# raspdoor.net
KiCad netlist of a schematic drawn in EAGLE
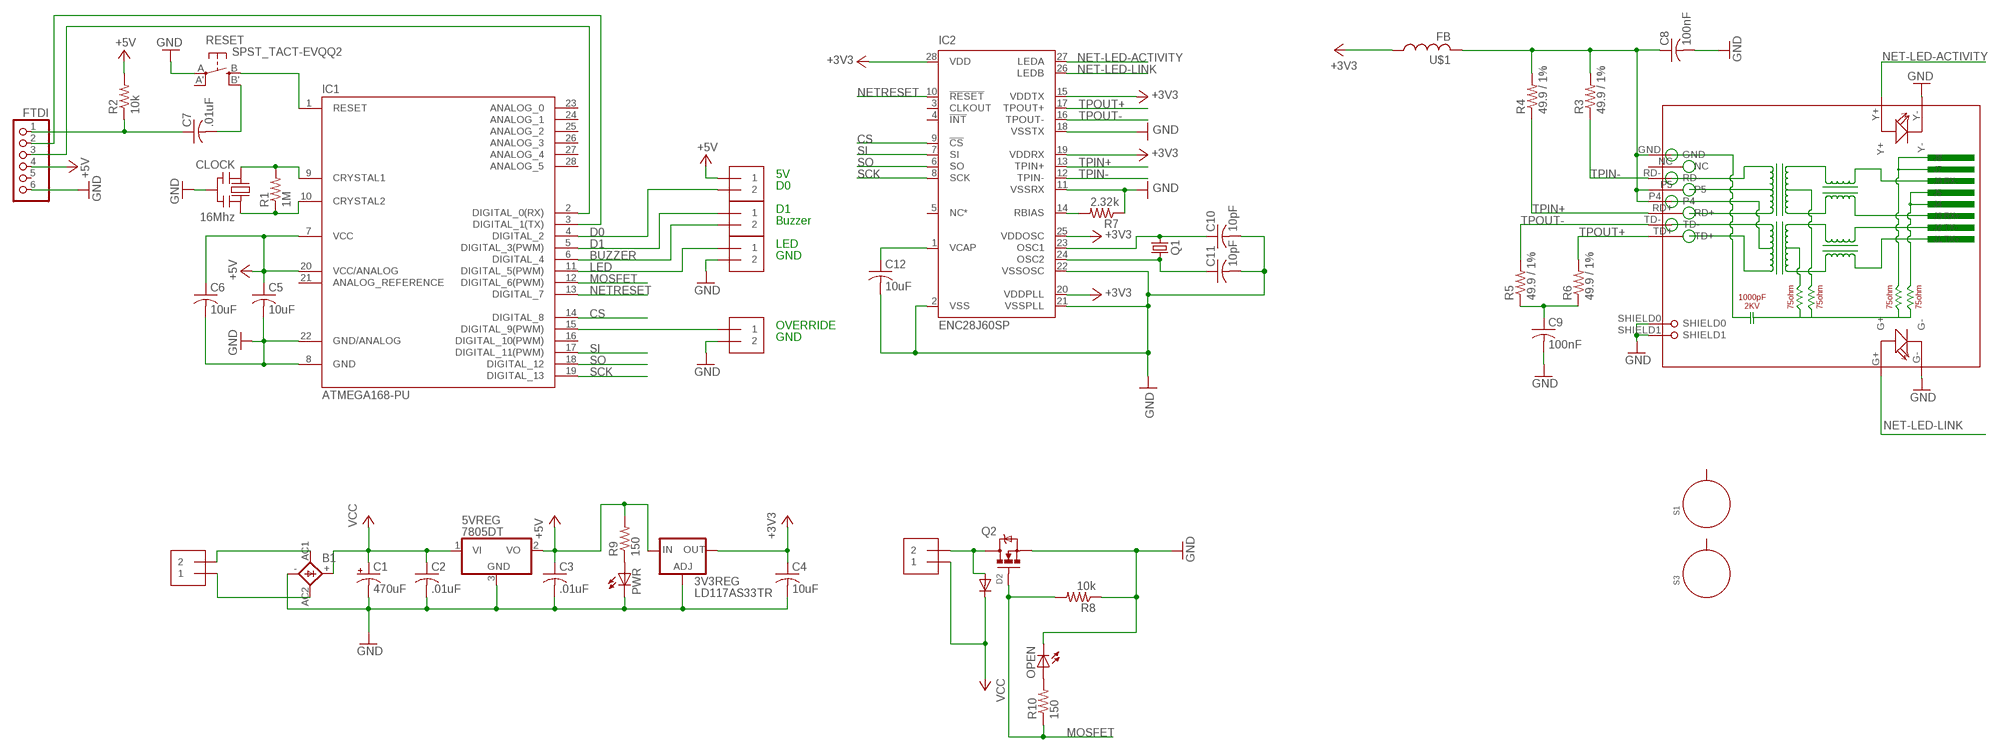
[diagram p0: schematic, sheet 1]

(export (version "E")
  (design (tool "Eeschema 10.0.6"))
  (components
    (comp (ref "3V3REG")
      (value "LD117AS33TR")
      (footprint "eagle-import:SOT223")
      (libsource (lib "eagle-import") (part "LD117A?S33TR"))
    )
    (comp (ref "5VREG")
      (value "7805DT")
      (footprint "eagle-import:TO252")
      (libsource (lib "eagle-import") (part "78DT05"))
    )
    (comp (ref "B1")
      (value "2KBB")
      (footprint "eagle-import:2KBB")
      (libsource (lib "eagle-import") (part "2KBB"))
    )
    (comp (ref "C1")
      (value "470uF")
      (footprint "eagle-import:153CLV-0810")
      (libsource (lib "eagle-import") (part "CPOL-US153CLV-0810"))
    )
    (comp (ref "C2")
      (value ".01uF")
      (footprint "eagle-import:C0805")
      (libsource (lib "eagle-import") (part "C-USC0805"))
    )
    (comp (ref "C3")
      (value ".01uF")
      (footprint "eagle-import:C0805")
      (libsource (lib "eagle-import") (part "C-USC0805"))
    )
    (comp (ref "C4")
      (value "10uF")
      (footprint "eagle-import:C0805")
      (libsource (lib "eagle-import") (part "C-USC0805"))
    )
    (comp (ref "C5")
      (value "10uF")
      (footprint "eagle-import:C0805")
      (libsource (lib "eagle-import") (part "C-USC0805"))
    )
    (comp (ref "C6")
      (value "10uF")
      (footprint "eagle-import:C0805")
      (libsource (lib "eagle-import") (part "C-USC0805"))
    )
    (comp (ref "C7")
      (value ".01uF")
      (footprint "eagle-import:C0805")
      (libsource (lib "eagle-import") (part "C-USC0805"))
    )
    (comp (ref "C8")
      (value "100nF")
      (footprint "eagle-import:C0805")
      (libsource (lib "eagle-import") (part "C-USC0805"))
    )
    (comp (ref "C9")
      (value "100nF")
      (footprint "eagle-import:C0805")
      (libsource (lib "eagle-import") (part "C-USC0805"))
    )
    (comp (ref "C10")
      (value "10pF")
      (footprint "eagle-import:C0805")
      (libsource (lib "eagle-import") (part "C-USC0805"))
    )
    (comp (ref "C11")
      (value "10pF")
      (footprint "eagle-import:C0805")
      (libsource (lib "eagle-import") (part "C-USC0805"))
    )
    (comp (ref "C12")
      (value "10uF")
      (footprint "eagle-import:C0805")
      (libsource (lib "eagle-import") (part "C-USC0805"))
    )
    (comp (ref "CLOCK")
      (value "16Mhz")
      (footprint "eagle-import:CERM_OSC")
      (libsource (lib "eagle-import") (part "CERMOSCILL-THM"))
    )
    (comp (ref "D2")
      (value "DIODESMA")
      (footprint "eagle-import:SMADIODE")
      (libsource (lib "eagle-import") (part "DIODESMA"))
    )
    (comp (ref "FTDI")
      (value "PINHD-1X6")
      (footprint "eagle-import:1X06")
      (libsource (lib "eagle-import") (part "PINHD-1X6"))
    )
    (comp (ref "IC1")
      (value "ATMEGA168-PU")
      (footprint "eagle-import:DIL28-3")
      (libsource (lib "eagle-import") (part "ATMEGA168-PU"))
    )
    (comp (ref "IC2")
      (value "ENC28J60SP")
      (footprint "eagle-import:DIL28-3")
      (fields (field (name "MF") "MICROCHIP") (field (name "MPN") "ENC28J60/SP"))
      (libsource (lib "eagle-import") (part "ENC28J60SP"))
    )
    (comp (ref "J1")
      (value "1X2-3.5MM")
      (footprint "eagle-import:1X2-3.5MM")
      (libsource (lib "eagle-import") (part "1X2-3.5MM"))
    )
    (comp (ref "J2")
      (value "1X2-3.5MM")
      (footprint "eagle-import:1X2-3.5MM")
      (libsource (lib "eagle-import") (part "1X2-3.5MM"))
    )
    (comp (ref "J3")
      (value "1X2-3.5MM")
      (footprint "eagle-import:1X2-3.5MM")
      (libsource (lib "eagle-import") (part "1X2-3.5MM"))
    )
    (comp (ref "J4")
      (value "1X2-3.5MM")
      (footprint "eagle-import:1X2-3.5MM")
      (libsource (lib "eagle-import") (part "1X2-3.5MM"))
    )
    (comp (ref "J5")
      (value "1X2-3.5MM")
      (footprint "eagle-import:1X2-3.5MM")
      (libsource (lib "eagle-import") (part "1X2-3.5MM"))
    )
    (comp (ref "J6")
      (value "1X2-3.5MM")
      (footprint "eagle-import:1X2-3.5MM")
      (libsource (lib "eagle-import") (part "1X2-3.5MM"))
    )
    (comp (ref "OPEN")
      (value "LEDCHIPLED_0805")
      (footprint "eagle-import:CHIPLED_0805")
      (libsource (lib "eagle-import") (part "LEDCHIPLED_0805"))
    )
    (comp (ref "PWR")
      (value "LEDCHIPLED_0805")
      (footprint "eagle-import:CHIPLED_0805")
      (libsource (lib "eagle-import") (part "LEDCHIPLED_0805"))
    )
    (comp (ref "Q1")
      (value "CRYSTALHC49S")
      (footprint "eagle-import:HC49_S")
      (libsource (lib "eagle-import") (part "CRYSTALHC49S"))
    )
    (comp (ref "Q2")
      (value "MOSFET-NCHANNELFQP30N06L")
      (footprint "eagle-import:TO220V")
      (libsource (lib "eagle-import") (part "MOSFET-NCHANNELFQP30N06L"))
    )
    (comp (ref "R1")
      (value "1M")
      (footprint "eagle-import:R0805")
      (libsource (lib "eagle-import") (part "R-US_R0805"))
    )
    (comp (ref "R2")
      (value "10k")
      (footprint "eagle-import:R0805")
      (libsource (lib "eagle-import") (part "R-US_R0805"))
    )
    (comp (ref "R3")
      (value "49.9 / 1%")
      (footprint "eagle-import:R0805")
      (libsource (lib "eagle-import") (part "R-US_R0805"))
    )
    (comp (ref "R4")
      (value "49.9 / 1%")
      (footprint "eagle-import:R0805")
      (libsource (lib "eagle-import") (part "R-US_R0805"))
    )
    (comp (ref "R5")
      (value "49.9 / 1%")
      (footprint "eagle-import:R0805")
      (libsource (lib "eagle-import") (part "R-US_R0805"))
    )
    (comp (ref "R6")
      (value "49.9 / 1%")
      (footprint "eagle-import:R0805")
      (libsource (lib "eagle-import") (part "R-US_R0805"))
    )
    (comp (ref "R7")
      (value "2.32k")
      (footprint "eagle-import:R0805")
      (libsource (lib "eagle-import") (part "R-US_R0805"))
    )
    (comp (ref "R8")
      (value "10k")
      (footprint "eagle-import:R0805")
      (libsource (lib "eagle-import") (part "R-US_R0805"))
    )
    (comp (ref "R9")
      (value "150")
      (footprint "eagle-import:R0805")
      (libsource (lib "eagle-import") (part "R-US_R0805"))
    )
    (comp (ref "R10")
      (value "150")
      (footprint "eagle-import:R0805")
      (libsource (lib "eagle-import") (part "R-US_R0805"))
    )
    (comp (ref "RESET")
      (value "SPST_TACT-EVQQ2")
      (footprint "eagle-import:EVQ-Q2")
      (libsource (lib "eagle-import") (part "SPST_TACT-EVQQ2"))
    )
    (comp (ref "RJ1")
      (value "HR911105A")
      (footprint "eagle-import:HR911105A")
      (libsource (lib "eagle-import") (part "HR911105A"))
    )
    (comp (ref "S1")
      (value "STANDOFF_ELECTRICAL")
      (footprint "eagle-import:STANDOFF-ELECTRICAL")
      (libsource (lib "eagle-import") (part "STANDOFF_ELECTRICAL"))
    )
    (comp (ref "S3")
      (value "STANDOFF_ELECTRICAL")
      (footprint "eagle-import:STANDOFF-ELECTRICAL")
      (libsource (lib "eagle-import") (part "STANDOFF_ELECTRICAL"))
    )
    (comp (ref "U$1") (value "FB") (footprint "eagle-import:FB") (libsource (lib "eagle-import") (part "FB")))
  )
  (nets
    (net (code "1") (name "+3V3") (class "Default")
      (node (ref "3V3REG") (pin "4") (pinfunction "OUT_4") (pintype "passive"))
      (node (ref "C4") (pin "1") (pinfunction "1_1") (pintype "passive"))
      (node (ref "IC2") (pin "15") (pinfunction "VDDTX_15") (pintype "input"))
      (node (ref "IC2") (pin "19") (pinfunction "VDDRX_19") (pintype "input"))
      (node (ref "IC2") (pin "20") (pinfunction "VDDPLL_20") (pintype "input"))
      (node (ref "IC2") (pin "25") (pinfunction "VDDOSC_25") (pintype "input"))
      (node (ref "IC2") (pin "28") (pinfunction "VDD_28") (pintype "input"))
      (node (ref "U$1") (pin "P$1") (pinfunction "1_P$1") (pintype "passive"))
    )
    (net (code "2") (name "+5V") (class "Default")
      (node (ref "3V3REG") (pin "3") (pinfunction "IN_3") (pintype "input"))
      (node (ref "5VREG") (pin "2") (pinfunction "VO_2") (pintype "passive"))
      (node (ref "C3") (pin "1") (pinfunction "1_1") (pintype "passive"))
      (node (ref "C5") (pin "1") (pinfunction "1_1") (pintype "passive"))
      (node (ref "C6") (pin "1") (pinfunction "1_1") (pintype "passive"))
      (node (ref "FTDI") (pin "4") (pinfunction "4_4") (pintype "passive"))
      (node (ref "IC1") (pin "20") (pinfunction "VCC/ANALOG_20") (pintype "passive"))
      (node (ref "IC1") (pin "7") (pinfunction "VCC_7") (pintype "power_in"))
      (node (ref "J3") (pin "1") (pinfunction "1_1") (pintype "passive"))
      (node (ref "R2") (pin "2") (pinfunction "2_2") (pintype "passive"))
      (node (ref "R9") (pin "2") (pinfunction "2_2") (pintype "passive"))
    )
    (net (code "3") (name "/BUZZER") (class "Default")
      (node (ref "IC1") (pin "6") (pinfunction "DIGITAL_4_6") (pintype "bidirectional"))
      (node (ref "J4") (pin "2") (pinfunction "2_2") (pintype "passive"))
    )
    (net (code "4") (name "/CS") (class "Default")
      (node (ref "IC1") (pin "14") (pinfunction "DIGITAL_8_14") (pintype "bidirectional"))
      (node (ref "IC2") (pin "9") (pinfunction "~{CS}_9") (pintype "input"))
    )
    (net (code "5") (name "/D0") (class "Default")
      (node (ref "IC1") (pin "4") (pinfunction "DIGITAL_2_4") (pintype "bidirectional"))
      (node (ref "J3") (pin "2") (pinfunction "2_2") (pintype "passive"))
    )
    (net (code "6") (name "/D1") (class "Default")
      (node (ref "IC1") (pin "5") (pinfunction "DIGITAL_3(PWM)_5") (pintype "bidirectional"))
      (node (ref "J4") (pin "1") (pinfunction "1_1") (pintype "passive"))
    )
    (net (code "7") (name "/LED") (class "Default")
      (node (ref "IC1") (pin "11") (pinfunction "DIGITAL_5(PWM)_11") (pintype "bidirectional"))
      (node (ref "J5") (pin "1") (pinfunction "1_1") (pintype "passive"))
    )
    (net (code "8") (name "/MOSFET") (class "Default")
      (node (ref "IC1") (pin "12") (pinfunction "DIGITAL_6(PWM)_12") (pintype "bidirectional"))
      (node (ref "Q2") (pin "1") (pinfunction "G_1") (pintype "passive"))
      (node (ref "R10") (pin "1") (pinfunction "1_1") (pintype "passive"))
      (node (ref "R8") (pin "2") (pinfunction "2_2") (pintype "passive"))
    )
    (net (code "9") (name "/NET-LED-ACTIVITY") (class "Default")
      (node (ref "IC2") (pin "27") (pinfunction "LEDA_27") (pintype "output"))
      (node (ref "RJ1") (pin "Y+") (pinfunction "Y+_Y+") (pintype "bidirectional"))
    )
    (net (code "10") (name "/NET-LED-LINK") (class "Default")
      (node (ref "IC2") (pin "26") (pinfunction "LEDB_26") (pintype "output"))
      (node (ref "RJ1") (pin "G+") (pinfunction "G+_G+") (pintype "bidirectional"))
    )
    (net (code "11") (name "/NETRESET") (class "Default")
      (node (ref "IC1") (pin "13") (pinfunction "DIGITAL_7_13") (pintype "bidirectional"))
      (node (ref "IC2") (pin "10") (pinfunction "~{RESET}_10") (pintype "input"))
    )
    (net (code "12") (name "/SCK") (class "Default")
      (node (ref "IC1") (pin "19") (pinfunction "DIGITAL_13_19") (pintype "bidirectional"))
      (node (ref "IC2") (pin "8") (pinfunction "SCK_8") (pintype "input"))
    )
    (net (code "13") (name "/SI") (class "Default")
      (node (ref "IC1") (pin "17") (pinfunction "DIGITAL_11(PWM)_17") (pintype "bidirectional"))
      (node (ref "IC2") (pin "7") (pinfunction "SI_7") (pintype "input"))
    )
    (net (code "14") (name "/SO") (class "Default")
      (node (ref "IC1") (pin "18") (pinfunction "DIGITAL_12_18") (pintype "bidirectional"))
      (node (ref "IC2") (pin "6") (pinfunction "SO_6") (pintype "output"))
    )
    (net (code "15") (name "/TPIN+") (class "Default")
      (node (ref "IC2") (pin "13") (pinfunction "TPIN+_13") (pintype "input"))
      (node (ref "R4") (pin "1") (pinfunction "1_1") (pintype "passive"))
      (node (ref "RJ1") (pin "RD+") (pinfunction "RD+_RD+") (pintype "bidirectional"))
    )
    (net (code "16") (name "/TPIN-") (class "Default")
      (node (ref "IC2") (pin "12") (pinfunction "TPIN-_12") (pintype "input"))
      (node (ref "R3") (pin "1") (pinfunction "1_1") (pintype "passive"))
      (node (ref "RJ1") (pin "RD-") (pinfunction "RD-_RD-") (pintype "bidirectional"))
    )
    (net (code "17") (name "/TPOUT+") (class "Default")
      (node (ref "IC2") (pin "17") (pinfunction "TPOUT+_17") (pintype "output"))
      (node (ref "R6") (pin "2") (pinfunction "2_2") (pintype "passive"))
      (node (ref "RJ1") (pin "TD+") (pinfunction "TD+_TD+") (pintype "bidirectional"))
    )
    (net (code "18") (name "/TPOUT-") (class "Default")
      (node (ref "IC2") (pin "16") (pinfunction "TPOUT-_16") (pintype "output"))
      (node (ref "R5") (pin "2") (pinfunction "2_2") (pintype "passive"))
      (node (ref "RJ1") (pin "TD-") (pinfunction "TD-_TD-") (pintype "bidirectional"))
    )
    (net (code "19") (name "GND") (class "Default")
      (node (ref "3V3REG") (pin "1") (pinfunction "ADJ_1") (pintype "input"))
      (node (ref "5VREG") (pin "3") (pinfunction "GND_3") (pintype "passive"))
      (node (ref "B1") (pin "-") (pinfunction "-_-") (pintype "passive"))
      (node (ref "C1") (pin "-") (pinfunction "-_-") (pintype "passive"))
      (node (ref "C10") (pin "2") (pinfunction "2_2") (pintype "passive"))
      (node (ref "C11") (pin "2") (pinfunction "2_2") (pintype "passive"))
      (node (ref "C12") (pin "2") (pinfunction "2_2") (pintype "passive"))
      (node (ref "C2") (pin "2") (pinfunction "2_2") (pintype "passive"))
      (node (ref "C3") (pin "2") (pinfunction "2_2") (pintype "passive"))
      (node (ref "C4") (pin "2") (pinfunction "2_2") (pintype "passive"))
      (node (ref "C5") (pin "2") (pinfunction "2_2") (pintype "passive"))
      (node (ref "C6") (pin "2") (pinfunction "2_2") (pintype "passive"))
      (node (ref "C8") (pin "2") (pinfunction "2_2") (pintype "passive"))
      (node (ref "C9") (pin "2") (pinfunction "2_2") (pintype "passive"))
      (node (ref "CLOCK") (pin "P$2") (pinfunction "GND_P$2") (pintype "bidirectional"))
      (node (ref "FTDI") (pin "6") (pinfunction "6_6") (pintype "passive"))
      (node (ref "IC1") (pin "22") (pinfunction "GND/ANALOG_22") (pintype "power_in"))
      (node (ref "IC1") (pin "8") (pinfunction "GND_8") (pintype "power_in"))
      (node (ref "IC2") (pin "11") (pinfunction "VSSRX_11") (pintype "input"))
      (node (ref "IC2") (pin "18") (pinfunction "VSSTX_18") (pintype "input"))
      (node (ref "IC2") (pin "2") (pinfunction "VSS_2") (pintype "input"))
      (node (ref "IC2") (pin "21") (pinfunction "VSSPLL_21") (pintype "input"))
      (node (ref "IC2") (pin "22") (pinfunction "VSSOSC_22") (pintype "input"))
      (node (ref "J5") (pin "2") (pinfunction "2_2") (pintype "passive"))
      (node (ref "J6") (pin "2") (pinfunction "2_2") (pintype "passive"))
      (node (ref "OPEN") (pin "C") (pinfunction "C_C") (pintype "passive"))
      (node (ref "PWR") (pin "C") (pinfunction "C_C") (pintype "passive"))
      (node (ref "Q2") (pin "3") (pinfunction "S_3") (pintype "passive"))
      (node (ref "R7") (pin "1") (pinfunction "1_1") (pintype "passive"))
      (node (ref "R8") (pin "1") (pinfunction "1_1") (pintype "passive"))
      (node (ref "RESET") (pin "A") (pinfunction "P_A") (pintype "passive"))
      (node (ref "RJ1") (pin "G-") (pinfunction "G-_G-") (pintype "bidirectional"))
      (node (ref "RJ1") (pin "SHIELD0") (pinfunction "SHIELD0_SHIELD0") (pintype "bidirectional"))
      (node (ref "RJ1") (pin "SHIELD1") (pinfunction "SHIELD1_SHIELD1") (pintype "bidirectional"))
      (node (ref "RJ1") (pin "Y-") (pinfunction "Y-_Y-") (pintype "bidirectional"))
    )
    (net (code "20") (name "Net-(B1-PadAC1)") (class "Default")
      (node (ref "B1") (pin "AC1") (pinfunction "AC1_AC1") (pintype "passive"))
      (node (ref "J1") (pin "2") (pinfunction "2_2") (pintype "passive"))
    )
    (net (code "21") (name "Net-(B1-PadAC2)") (class "Default")
      (node (ref "B1") (pin "AC2") (pinfunction "AC2_AC2") (pintype "passive"))
      (node (ref "J1") (pin "1") (pinfunction "1_1") (pintype "passive"))
    )
    (net (code "22") (name "Net-(C7-Pad1)") (class "Default")
      (node (ref "C7") (pin "1") (pinfunction "1_1") (pintype "passive"))
      (node (ref "FTDI") (pin "1") (pinfunction "1_1") (pintype "passive"))
      (node (ref "R2") (pin "1") (pinfunction "1_1") (pintype "passive"))
    )
    (net (code "23") (name "Net-(C9-Pad1)") (class "Default")
      (node (ref "C9") (pin "1") (pinfunction "1_1") (pintype "passive"))
      (node (ref "R5") (pin "1") (pinfunction "1_1") (pintype "passive"))
      (node (ref "R6") (pin "1") (pinfunction "1_1") (pintype "passive"))
    )
    (net (code "24") (name "Net-(CLOCK-IN)") (class "Default")
      (node (ref "CLOCK") (pin "P$1") (pinfunction "IN_P$1") (pintype "bidirectional"))
      (node (ref "IC1") (pin "9") (pinfunction "CRYSTAL1_9") (pintype "bidirectional"))
      (node (ref "R1") (pin "2") (pinfunction "2_2") (pintype "passive"))
    )
    (net (code "25") (name "Net-(CLOCK-OUT)") (class "Default")
      (node (ref "CLOCK") (pin "P$3") (pinfunction "OUT_P$3") (pintype "bidirectional"))
      (node (ref "IC1") (pin "10") (pinfunction "CRYSTAL2_10") (pintype "bidirectional"))
      (node (ref "R1") (pin "1") (pinfunction "1_1") (pintype "passive"))
    )
    (net (code "26") (name "Net-(IC1-DIGITAL_0(RX))") (class "Default")
      (node (ref "FTDI") (pin "3") (pinfunction "3_3") (pintype "passive"))
      (node (ref "IC1") (pin "2") (pinfunction "DIGITAL_0(RX)_2") (pintype "bidirectional"))
    )
    (net (code "27") (name "Net-(IC1-DIGITAL_1(TX))") (class "Default")
      (node (ref "FTDI") (pin "2") (pinfunction "2_2") (pintype "passive"))
      (node (ref "IC1") (pin "3") (pinfunction "DIGITAL_1(TX)_3") (pintype "bidirectional"))
    )
    (net (code "28") (name "Net-(IC1-DIGITAL_9(PWM))") (class "Default")
      (node (ref "IC1") (pin "15") (pinfunction "DIGITAL_9(PWM)_15") (pintype "bidirectional"))
      (node (ref "J6") (pin "1") (pinfunction "1_1") (pintype "passive"))
    )
    (net (code "29") (name "Net-(IC1-RESET)") (class "Default")
      (node (ref "IC1") (pin "1") (pinfunction "RESET_1") (pintype "bidirectional"))
      (node (ref "RESET") (pin "B") (pinfunction "S_B") (pintype "passive"))
    )
    (net (code "30") (name "Net-(IC2-OSC1)") (class "Default")
      (node (ref "C10") (pin "1") (pinfunction "1_1") (pintype "passive"))
      (node (ref "IC2") (pin "23") (pinfunction "OSC1_23") (pintype "input"))
      (node (ref "Q1") (pin "1") (pinfunction "1_1") (pintype "passive"))
    )
    (net (code "31") (name "Net-(IC2-OSC2)") (class "Default")
      (node (ref "C11") (pin "1") (pinfunction "1_1") (pintype "passive"))
      (node (ref "IC2") (pin "24") (pinfunction "OSC2_24") (pintype "output"))
      (node (ref "Q1") (pin "2") (pinfunction "2_2") (pintype "passive"))
    )
    (net (code "32") (name "Net-(IC2-RBIAS)") (class "Default")
      (node (ref "IC2") (pin "14") (pinfunction "RBIAS_14") (pintype "input"))
      (node (ref "R7") (pin "2") (pinfunction "2_2") (pintype "passive"))
    )
    (net (code "33") (name "Net-(IC2-VCAP)") (class "Default")
      (node (ref "C12") (pin "1") (pinfunction "1_1") (pintype "passive"))
      (node (ref "IC2") (pin "1") (pinfunction "VCAP_1") (pintype "input"))
    )
    (net (code "34") (name "Net-(OPEN-PadA)") (class "Default")
      (node (ref "OPEN") (pin "A") (pinfunction "A_A") (pintype "passive"))
      (node (ref "R10") (pin "2") (pinfunction "2_2") (pintype "passive"))
    )
    (net (code "35") (name "Net-(PWR-PadA)") (class "Default")
      (node (ref "PWR") (pin "A") (pinfunction "A_A") (pintype "passive"))
      (node (ref "R9") (pin "1") (pinfunction "1_1") (pintype "passive"))
    )
    (net (code "36") (name "Net-(Q2-D)") (class "Default")
      (node (ref "D2") (pin "A") (pinfunction "A_A") (pintype "passive"))
      (node (ref "J2") (pin "2") (pinfunction "2_2") (pintype "passive"))
      (node (ref "Q2") (pin "2") (pinfunction "D_2") (pintype "passive"))
    )
    (net (code "37") (name "Net-(RESET-S1)") (class "Default")
      (node (ref "C7") (pin "2") (pinfunction "2_2") (pintype "passive"))
      (node (ref "RESET") (pin "B'") (pinfunction "S1_B'") (pintype "passive"))
    )
    (net (code "38") (name "Net-(U$1-2)") (class "Default")
      (node (ref "C8") (pin "1") (pinfunction "1_1") (pintype "passive"))
      (node (ref "R3") (pin "2") (pinfunction "2_2") (pintype "passive"))
      (node (ref "R4") (pin "2") (pinfunction "2_2") (pintype "passive"))
      (node (ref "RJ1") (pin "GND") (pinfunction "GND_GND") (pintype "bidirectional"))
      (node (ref "RJ1") (pin "P4") (pinfunction "P4_P4") (pintype "bidirectional"))
      (node (ref "RJ1") (pin "P5") (pinfunction "P5_P5") (pintype "bidirectional"))
      (node (ref "U$1") (pin "P$2") (pinfunction "2_P$2") (pintype "passive"))
    )
    (net (code "39") (name "VCC") (class "Default")
      (node (ref "5VREG") (pin "1") (pinfunction "VI_1") (pintype "input"))
      (node (ref "B1") (pin "+") (pinfunction "+_+") (pintype "passive"))
      (node (ref "C1") (pin "+") (pinfunction "+_+") (pintype "passive"))
      (node (ref "C2") (pin "1") (pinfunction "1_1") (pintype "passive"))
      (node (ref "D2") (pin "C") (pinfunction "C_C") (pintype "passive"))
      (node (ref "J2") (pin "1") (pinfunction "1_1") (pintype "passive"))
    )
    (net (code "40") (name "unconnected-(FTDI-Pad5)") (class "Default")
      (node (ref "FTDI") (pin "5") (pinfunction "5_5") (pintype "passive"))
    )
    (net (code "41") (name "unconnected-(IC1-ANALOG_0-Pad23)") (class "Default")
      (node (ref "IC1") (pin "23") (pinfunction "ANALOG_0_23") (pintype "bidirectional"))
    )
    (net (code "42") (name "unconnected-(IC1-ANALOG_1-Pad24)") (class "Default")
      (node (ref "IC1") (pin "24") (pinfunction "ANALOG_1_24") (pintype "bidirectional"))
    )
    (net (code "43") (name "unconnected-(IC1-ANALOG_2-Pad25)") (class "Default")
      (node (ref "IC1") (pin "25") (pinfunction "ANALOG_2_25") (pintype "bidirectional"))
    )
    (net (code "44") (name "unconnected-(IC1-ANALOG_3-Pad26)") (class "Default")
      (node (ref "IC1") (pin "26") (pinfunction "ANALOG_3_26") (pintype "bidirectional"))
    )
    (net (code "45") (name "unconnected-(IC1-ANALOG_4-Pad27)") (class "Default")
      (node (ref "IC1") (pin "27") (pinfunction "ANALOG_4_27") (pintype "bidirectional"))
    )
    (net (code "46") (name "unconnected-(IC1-ANALOG_5-Pad28)") (class "Default")
      (node (ref "IC1") (pin "28") (pinfunction "ANALOG_5_28") (pintype "bidirectional"))
    )
    (net (code "47") (name "unconnected-(IC1-ANALOG_REFERENCE-Pad21)") (class "Default")
      (node (ref "IC1") (pin "21") (pinfunction "ANALOG_REFERENCE_21") (pintype "passive"))
    )
    (net (code "48") (name "unconnected-(IC1-DIGITAL_10(PWM)-Pad16)") (class "Default")
      (node (ref "IC1") (pin "16") (pinfunction "DIGITAL_10(PWM)_16") (pintype "bidirectional"))
    )
    (net (code "49") (name "unconnected-(IC2-CLKOUT-Pad3)") (class "Default")
      (node (ref "IC2") (pin "3") (pinfunction "CLKOUT_3") (pintype "output"))
    )
    (net (code "50") (name "unconnected-(IC2-NC*-Pad5)") (class "Default")
      (node (ref "IC2") (pin "5") (pinfunction "NC*_5") (pintype "output"))
    )
    (net (code "51") (name "unconnected-(IC2-~{INT}-Pad4)") (class "Default")
      (node (ref "IC2") (pin "4") (pinfunction "~{INT}_4") (pintype "output"))
    )
    (net (code "52") (name "unconnected-(RESET-P1-PadA')") (class "Default")
      (node (ref "RESET") (pin "A'") (pinfunction "P1_A'") (pintype "passive"))
    )
    (net (code "53") (name "unconnected-(RJ1-PadNC)") (class "Default")
      (node (ref "RJ1") (pin "NC") (pinfunction "NC_NC") (pintype "bidirectional"))
    )
    (net (code "54") (name "unconnected-(S1-P$1-PadP1)") (class "Default")
      (node (ref "S1") (pin "P1") (pinfunction "P$1_P1") (pintype "bidirectional"))
    )
    (net (code "55") (name "unconnected-(S3-P$1-PadP1)") (class "Default")
      (node (ref "S3") (pin "P1") (pinfunction "P$1_P1") (pintype "bidirectional"))
    )
  )
)
